# Core_Analogue_Inputs.net
KiCad netlist of a schematic drawn in Altium Designer
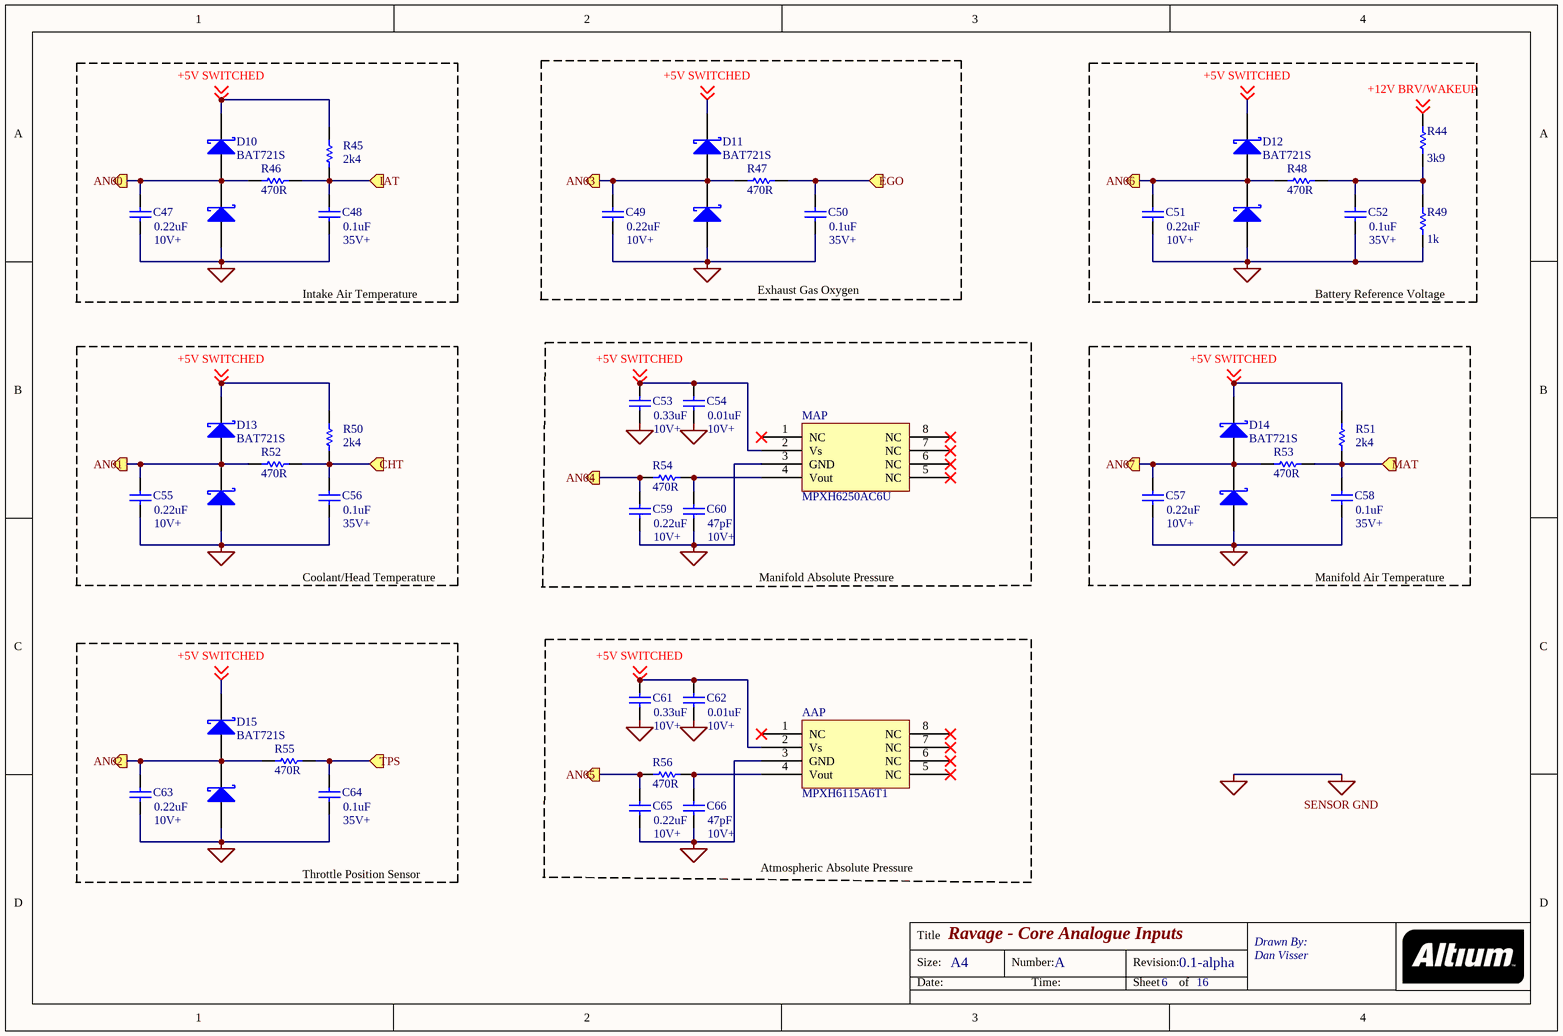
[diagram p0: Core Analogue Inputs.SchDoc]

(export (version "E")
  (design (tool "Eeschema 10.0.6"))
  (components
    (comp (ref "AAP")
      (value "MPXH6115A6T1")
      (libsource (lib "FreeEMS Schematic Library") (part "MPXH6115A6T1"))
    )
    (comp (ref "C47")
      (value "0.22uF")
      (footprint "RAD-0.3")
      (description "Capacitor")
      (fields (field (name "PUBLISHER") "Altium Limited"))
      (libsource (lib "Miscellaneous Devices") (part "Cap"))
    )
    (comp (ref "C48")
      (value "0.1uF")
      (footprint "RAD-0.3")
      (description "Capacitor")
      (fields (field (name "PUBLISHER") "Altium Limited"))
      (libsource (lib "Miscellaneous Devices") (part "Cap"))
    )
    (comp (ref "C49")
      (value "0.22uF")
      (footprint "RAD-0.3")
      (description "Capacitor")
      (fields (field (name "PUBLISHER") "Altium Limited"))
      (libsource (lib "Miscellaneous Devices") (part "Cap"))
    )
    (comp (ref "C50")
      (value "0.1uF")
      (footprint "RAD-0.3")
      (description "Capacitor")
      (fields (field (name "PUBLISHER") "Altium Limited"))
      (libsource (lib "Miscellaneous Devices") (part "Cap"))
    )
    (comp (ref "C51")
      (value "0.22uF")
      (footprint "RAD-0.3")
      (description "Capacitor")
      (fields (field (name "PUBLISHER") "Altium Limited"))
      (libsource (lib "Miscellaneous Devices") (part "Cap"))
    )
    (comp (ref "C52")
      (value "0.1uF")
      (footprint "RAD-0.3")
      (description "Capacitor")
      (fields (field (name "PUBLISHER") "Altium Limited"))
      (libsource (lib "Miscellaneous Devices") (part "Cap"))
    )
    (comp (ref "C53")
      (value "0.33uF")
      (footprint "RAD-0.3")
      (description "Capacitor")
      (fields (field (name "PUBLISHER") "Altium Limited"))
      (libsource (lib "Miscellaneous Devices") (part "Cap"))
    )
    (comp (ref "C54")
      (value "0.01uF")
      (footprint "RAD-0.3")
      (description "Capacitor")
      (fields (field (name "PUBLISHER") "Altium Limited"))
      (libsource (lib "Miscellaneous Devices") (part "Cap"))
    )
    (comp (ref "C55")
      (value "0.22uF")
      (footprint "RAD-0.3")
      (description "Capacitor")
      (fields (field (name "PUBLISHER") "Altium Limited"))
      (libsource (lib "Miscellaneous Devices") (part "Cap"))
    )
    (comp (ref "C56")
      (value "0.1uF")
      (footprint "RAD-0.3")
      (description "Capacitor")
      (fields (field (name "PUBLISHER") "Altium Limited"))
      (libsource (lib "Miscellaneous Devices") (part "Cap"))
    )
    (comp (ref "C57")
      (value "0.22uF")
      (footprint "RAD-0.3")
      (description "Capacitor")
      (fields (field (name "PUBLISHER") "Altium Limited"))
      (libsource (lib "Miscellaneous Devices") (part "Cap"))
    )
    (comp (ref "C58")
      (value "0.1uF")
      (footprint "RAD-0.3")
      (description "Capacitor")
      (fields (field (name "PUBLISHER") "Altium Limited"))
      (libsource (lib "Miscellaneous Devices") (part "Cap"))
    )
    (comp (ref "C59")
      (value "0.22uF")
      (footprint "RAD-0.3")
      (description "Capacitor")
      (fields (field (name "PUBLISHER") "Altium Limited"))
      (libsource (lib "Miscellaneous Devices") (part "Cap"))
    )
    (comp (ref "C60")
      (value "47pF")
      (footprint "RAD-0.3")
      (description "Capacitor")
      (fields (field (name "PUBLISHER") "Altium Limited"))
      (libsource (lib "Miscellaneous Devices") (part "Cap"))
    )
    (comp (ref "C61")
      (value "0.33uF")
      (footprint "RAD-0.3")
      (description "Capacitor")
      (fields (field (name "PUBLISHER") "Altium Limited"))
      (libsource (lib "Miscellaneous Devices") (part "Cap"))
    )
    (comp (ref "C62")
      (value "0.01uF")
      (footprint "RAD-0.3")
      (description "Capacitor")
      (fields (field (name "PUBLISHER") "Altium Limited"))
      (libsource (lib "Miscellaneous Devices") (part "Cap"))
    )
    (comp (ref "C63")
      (value "0.22uF")
      (footprint "RAD-0.3")
      (description "Capacitor")
      (fields (field (name "PUBLISHER") "Altium Limited"))
      (libsource (lib "Miscellaneous Devices") (part "Cap"))
    )
    (comp (ref "C64")
      (value "0.1uF")
      (footprint "RAD-0.3")
      (description "Capacitor")
      (fields (field (name "PUBLISHER") "Altium Limited"))
      (libsource (lib "Miscellaneous Devices") (part "Cap"))
    )
    (comp (ref "C65")
      (value "0.22uF")
      (footprint "RAD-0.3")
      (description "Capacitor")
      (fields (field (name "PUBLISHER") "Altium Limited"))
      (libsource (lib "Miscellaneous Devices") (part "Cap"))
    )
    (comp (ref "C66")
      (value "47pF")
      (footprint "RAD-0.3")
      (description "Capacitor")
      (fields (field (name "PUBLISHER") "Altium Limited"))
      (libsource (lib "Miscellaneous Devices") (part "Cap"))
    )
    (comp (ref "D10")
      (value "BAT721S")
      (description "DUAL SCHOTTKY DIODE")
      (libsource (lib "FreeEMS Schematic Library") (part "BAT721S"))
    )
    (comp (ref "D11")
      (value "BAT721S")
      (description "DUAL SCHOTTKY DIODE")
      (libsource (lib "FreeEMS Schematic Library") (part "BAT721S"))
    )
    (comp (ref "D12")
      (value "BAT721S")
      (description "DUAL SCHOTTKY DIODE")
      (libsource (lib "FreeEMS Schematic Library") (part "BAT721S"))
    )
    (comp (ref "D13")
      (value "BAT721S")
      (description "DUAL SCHOTTKY DIODE")
      (libsource (lib "FreeEMS Schematic Library") (part "BAT721S"))
    )
    (comp (ref "D14")
      (value "BAT721S")
      (description "DUAL SCHOTTKY DIODE")
      (libsource (lib "FreeEMS Schematic Library") (part "BAT721S"))
    )
    (comp (ref "D15")
      (value "BAT721S")
      (description "DUAL SCHOTTKY DIODE")
      (libsource (lib "FreeEMS Schematic Library") (part "BAT721S"))
    )
    (comp (ref "MAP")
      (value "MPXH6250AC6U")
      (libsource (lib "FreeEMS Schematic Library") (part "MPXH6250AC6U"))
    )
    (comp (ref "R44")
      (value "3k9")
      (footprint "AXIAL-0.3")
      (description "Resistor")
      (fields (field (name "PUBLISHER") "Altium Limited"))
      (libsource (lib "Miscellaneous Devices") (part "Res1"))
    )
    (comp (ref "R45")
      (value "2k4")
      (footprint "AXIAL-0.3")
      (description "Resistor")
      (fields (field (name "PUBLISHER") "Altium Limited"))
      (libsource (lib "Miscellaneous Devices") (part "Res1"))
    )
    (comp (ref "R46")
      (value "470R")
      (footprint "AXIAL-0.3")
      (description "Resistor")
      (fields (field (name "PUBLISHER") "Altium Limited"))
      (libsource (lib "Miscellaneous Devices") (part "Res1"))
    )
    (comp (ref "R47")
      (value "470R")
      (footprint "AXIAL-0.3")
      (description "Resistor")
      (fields (field (name "PUBLISHER") "Altium Limited"))
      (libsource (lib "Miscellaneous Devices") (part "Res1"))
    )
    (comp (ref "R48")
      (value "470R")
      (footprint "AXIAL-0.3")
      (description "Resistor")
      (fields (field (name "PUBLISHER") "Altium Limited"))
      (libsource (lib "Miscellaneous Devices") (part "Res1"))
    )
    (comp (ref "R49")
      (value "1k")
      (footprint "AXIAL-0.3")
      (description "Resistor")
      (fields (field (name "PUBLISHER") "Altium Limited"))
      (libsource (lib "Miscellaneous Devices") (part "Res1"))
    )
    (comp (ref "R50")
      (value "2k4")
      (footprint "AXIAL-0.3")
      (description "Resistor")
      (fields (field (name "PUBLISHER") "Altium Limited"))
      (libsource (lib "Miscellaneous Devices") (part "Res1"))
    )
    (comp (ref "R51")
      (value "2k4")
      (footprint "AXIAL-0.3")
      (description "Resistor")
      (fields (field (name "PUBLISHER") "Altium Limited"))
      (libsource (lib "Miscellaneous Devices") (part "Res1"))
    )
    (comp (ref "R52")
      (value "470R")
      (footprint "AXIAL-0.3")
      (description "Resistor")
      (fields (field (name "PUBLISHER") "Altium Limited"))
      (libsource (lib "Miscellaneous Devices") (part "Res1"))
    )
    (comp (ref "R53")
      (value "470R")
      (footprint "AXIAL-0.3")
      (description "Resistor")
      (fields (field (name "PUBLISHER") "Altium Limited"))
      (libsource (lib "Miscellaneous Devices") (part "Res1"))
    )
    (comp (ref "R54")
      (value "470R")
      (footprint "AXIAL-0.3")
      (description "Resistor")
      (fields (field (name "PUBLISHER") "Altium Limited"))
      (libsource (lib "Miscellaneous Devices") (part "Res1"))
    )
    (comp (ref "R55")
      (value "470R")
      (footprint "AXIAL-0.3")
      (description "Resistor")
      (fields (field (name "PUBLISHER") "Altium Limited"))
      (libsource (lib "Miscellaneous Devices") (part "Res1"))
    )
    (comp (ref "R56")
      (value "470R")
      (footprint "AXIAL-0.3")
      (description "Resistor")
      (fields (field (name "PUBLISHER") "Altium Limited"))
      (libsource (lib "Miscellaneous Devices") (part "Res1"))
    )
  )
  (nets
    (net (code "1") (name "+5V SWITCHED") (class "Default")
      (node (ref "AAP") (pin "2") (pinfunction "Vs_2") (pintype "passive"))
      (node (ref "C53") (pin "2") (pinfunction "2_2") (pintype "passive"))
      (node (ref "C54") (pin "2") (pinfunction "2_2") (pintype "passive"))
      (node (ref "C61") (pin "2") (pinfunction "2_2") (pintype "passive"))
      (node (ref "C62") (pin "2") (pinfunction "2_2") (pintype "passive"))
      (node (ref "D10") (pin "2") (pinfunction "K_2") (pintype "passive"))
      (node (ref "D11") (pin "2") (pinfunction "K_2") (pintype "passive"))
      (node (ref "D12") (pin "2") (pinfunction "K_2") (pintype "passive"))
      (node (ref "D13") (pin "2") (pinfunction "K_2") (pintype "passive"))
      (node (ref "D14") (pin "2") (pinfunction "K_2") (pintype "passive"))
      (node (ref "D15") (pin "2") (pinfunction "K_2") (pintype "passive"))
      (node (ref "MAP") (pin "2") (pinfunction "Vs_2") (pintype "passive"))
      (node (ref "R45") (pin "1") (pinfunction "1_1") (pintype "passive"))
      (node (ref "R50") (pin "1") (pinfunction "1_1") (pintype "passive"))
      (node (ref "R51") (pin "1") (pinfunction "1_1") (pintype "passive"))
    )
    (net (code "2") (name "+12V BRV{slash}WAKEUP") (class "Default")
      (node (ref "R44") (pin "2") (pinfunction "2_2") (pintype "passive"))
    )
    (net (code "3") (name "/AN00") (class "Default")
      (node (ref "C47") (pin "2") (pinfunction "2_2") (pintype "passive"))
      (node (ref "D10") (pin "3") (pinfunction "A2_3") (pintype "passive"))
      (node (ref "R46") (pin "1") (pinfunction "1_1") (pintype "passive"))
    )
    (net (code "4") (name "/AN01") (class "Default")
      (node (ref "C55") (pin "2") (pinfunction "2_2") (pintype "passive"))
      (node (ref "D13") (pin "3") (pinfunction "A2_3") (pintype "passive"))
      (node (ref "R52") (pin "1") (pinfunction "1_1") (pintype "passive"))
    )
    (net (code "5") (name "/AN02") (class "Default")
      (node (ref "C63") (pin "2") (pinfunction "2_2") (pintype "passive"))
      (node (ref "D15") (pin "3") (pinfunction "A2_3") (pintype "passive"))
      (node (ref "R55") (pin "1") (pinfunction "1_1") (pintype "passive"))
    )
    (net (code "6") (name "/AN03") (class "Default")
      (node (ref "C49") (pin "2") (pinfunction "2_2") (pintype "passive"))
      (node (ref "D11") (pin "3") (pinfunction "A2_3") (pintype "passive"))
      (node (ref "R47") (pin "1") (pinfunction "1_1") (pintype "passive"))
    )
    (net (code "7") (name "/AN04") (class "Default")
      (node (ref "C59") (pin "2") (pinfunction "2_2") (pintype "passive"))
      (node (ref "R54") (pin "1") (pinfunction "1_1") (pintype "passive"))
    )
    (net (code "8") (name "/AN05") (class "Default")
      (node (ref "C65") (pin "2") (pinfunction "2_2") (pintype "passive"))
      (node (ref "R56") (pin "1") (pinfunction "1_1") (pintype "passive"))
    )
    (net (code "9") (name "/AN06") (class "Default")
      (node (ref "C51") (pin "2") (pinfunction "2_2") (pintype "passive"))
      (node (ref "D12") (pin "3") (pinfunction "A2_3") (pintype "passive"))
      (node (ref "R48") (pin "1") (pinfunction "1_1") (pintype "passive"))
    )
    (net (code "10") (name "/AN07") (class "Default")
      (node (ref "C57") (pin "2") (pinfunction "2_2") (pintype "passive"))
      (node (ref "D14") (pin "3") (pinfunction "A2_3") (pintype "passive"))
      (node (ref "R53") (pin "1") (pinfunction "1_1") (pintype "passive"))
    )
    (net (code "11") (name "/CHT") (class "Default")
      (node (ref "C56") (pin "2") (pinfunction "2_2") (pintype "passive"))
      (node (ref "R50") (pin "2") (pinfunction "2_2") (pintype "passive"))
      (node (ref "R52") (pin "2") (pinfunction "2_2") (pintype "passive"))
    )
    (net (code "12") (name "/EGO") (class "Default")
      (node (ref "C50") (pin "2") (pinfunction "2_2") (pintype "passive"))
      (node (ref "R47") (pin "2") (pinfunction "2_2") (pintype "passive"))
    )
    (net (code "13") (name "/IAT") (class "Default")
      (node (ref "C48") (pin "2") (pinfunction "2_2") (pintype "passive"))
      (node (ref "R45") (pin "2") (pinfunction "2_2") (pintype "passive"))
      (node (ref "R46") (pin "2") (pinfunction "2_2") (pintype "passive"))
    )
    (net (code "14") (name "/MAT") (class "Default")
      (node (ref "C58") (pin "2") (pinfunction "2_2") (pintype "passive"))
      (node (ref "R51") (pin "2") (pinfunction "2_2") (pintype "passive"))
      (node (ref "R53") (pin "2") (pinfunction "2_2") (pintype "passive"))
    )
    (net (code "15") (name "/TPS") (class "Default")
      (node (ref "C64") (pin "2") (pinfunction "2_2") (pintype "passive"))
      (node (ref "R55") (pin "2") (pinfunction "2_2") (pintype "passive"))
    )
    (net (code "16") (name "<NO NET>") (class "Default")
      (node (ref "AAP") (pin "3") (pinfunction "GND_3") (pintype "passive"))
      (node (ref "C47") (pin "1") (pinfunction "1_1") (pintype "passive"))
      (node (ref "C48") (pin "1") (pinfunction "1_1") (pintype "passive"))
      (node (ref "C49") (pin "1") (pinfunction "1_1") (pintype "passive"))
      (node (ref "C50") (pin "1") (pinfunction "1_1") (pintype "passive"))
      (node (ref "C51") (pin "1") (pinfunction "1_1") (pintype "passive"))
      (node (ref "C52") (pin "1") (pinfunction "1_1") (pintype "passive"))
      (node (ref "C53") (pin "1") (pinfunction "1_1") (pintype "passive"))
      (node (ref "C54") (pin "1") (pinfunction "1_1") (pintype "passive"))
      (node (ref "C55") (pin "1") (pinfunction "1_1") (pintype "passive"))
      (node (ref "C56") (pin "1") (pinfunction "1_1") (pintype "passive"))
      (node (ref "C57") (pin "1") (pinfunction "1_1") (pintype "passive"))
      (node (ref "C58") (pin "1") (pinfunction "1_1") (pintype "passive"))
      (node (ref "C59") (pin "1") (pinfunction "1_1") (pintype "passive"))
      (node (ref "C60") (pin "1") (pinfunction "1_1") (pintype "passive"))
      (node (ref "C61") (pin "1") (pinfunction "1_1") (pintype "passive"))
      (node (ref "C62") (pin "1") (pinfunction "1_1") (pintype "passive"))
      (node (ref "C63") (pin "1") (pinfunction "1_1") (pintype "passive"))
      (node (ref "C64") (pin "1") (pinfunction "1_1") (pintype "passive"))
      (node (ref "C65") (pin "1") (pinfunction "1_1") (pintype "passive"))
      (node (ref "C66") (pin "1") (pinfunction "1_1") (pintype "passive"))
      (node (ref "D10") (pin "1") (pinfunction "A_1") (pintype "passive"))
      (node (ref "D11") (pin "1") (pinfunction "A_1") (pintype "passive"))
      (node (ref "D12") (pin "1") (pinfunction "A_1") (pintype "passive"))
      (node (ref "D13") (pin "1") (pinfunction "A_1") (pintype "passive"))
      (node (ref "D14") (pin "1") (pinfunction "A_1") (pintype "passive"))
      (node (ref "D15") (pin "1") (pinfunction "A_1") (pintype "passive"))
      (node (ref "MAP") (pin "3") (pinfunction "GND_3") (pintype "passive"))
      (node (ref "R49") (pin "1") (pinfunction "1_1") (pintype "passive"))
    )
    (net (code "17") (name "Net-(AAP-Vout)") (class "Default")
      (node (ref "AAP") (pin "4") (pinfunction "Vout_4") (pintype "passive"))
      (node (ref "C66") (pin "2") (pinfunction "2_2") (pintype "passive"))
      (node (ref "R56") (pin "2") (pinfunction "2_2") (pintype "passive"))
    )
    (net (code "18") (name "Net-(C52-Pad2)") (class "Default")
      (node (ref "C52") (pin "2") (pinfunction "2_2") (pintype "passive"))
      (node (ref "R44") (pin "1") (pinfunction "1_1") (pintype "passive"))
      (node (ref "R48") (pin "2") (pinfunction "2_2") (pintype "passive"))
      (node (ref "R49") (pin "2") (pinfunction "2_2") (pintype "passive"))
    )
    (net (code "19") (name "Net-(MAP-Vout)") (class "Default")
      (node (ref "C60") (pin "2") (pinfunction "2_2") (pintype "passive"))
      (node (ref "MAP") (pin "4") (pinfunction "Vout_4") (pintype "passive"))
      (node (ref "R54") (pin "2") (pinfunction "2_2") (pintype "passive"))
    )
    (net (code "20") (name "unconnected-(AAP-NC-Pad1)") (class "Default")
      (node (ref "AAP") (pin "1") (pinfunction "NC_1") (pintype "passive+no_connect"))
    )
    (net (code "21") (name "unconnected-(AAP-NC-Pad5)") (class "Default")
      (node (ref "AAP") (pin "5") (pinfunction "NC_5") (pintype "passive+no_connect"))
    )
    (net (code "22") (name "unconnected-(AAP-NC-Pad6)") (class "Default")
      (node (ref "AAP") (pin "6") (pinfunction "NC_6") (pintype "passive+no_connect"))
    )
    (net (code "23") (name "unconnected-(AAP-NC-Pad7)") (class "Default")
      (node (ref "AAP") (pin "7") (pinfunction "NC_7") (pintype "passive+no_connect"))
    )
    (net (code "24") (name "unconnected-(AAP-NC-Pad8)") (class "Default")
      (node (ref "AAP") (pin "8") (pinfunction "NC_8") (pintype "passive+no_connect"))
    )
    (net (code "25") (name "unconnected-(MAP-NC-Pad1)") (class "Default")
      (node (ref "MAP") (pin "1") (pinfunction "NC_1") (pintype "passive+no_connect"))
    )
    (net (code "26") (name "unconnected-(MAP-NC-Pad5)") (class "Default")
      (node (ref "MAP") (pin "5") (pinfunction "NC_5") (pintype "passive+no_connect"))
    )
    (net (code "27") (name "unconnected-(MAP-NC-Pad6)") (class "Default")
      (node (ref "MAP") (pin "6") (pinfunction "NC_6") (pintype "passive+no_connect"))
    )
    (net (code "28") (name "unconnected-(MAP-NC-Pad7)") (class "Default")
      (node (ref "MAP") (pin "7") (pinfunction "NC_7") (pintype "passive+no_connect"))
    )
    (net (code "29") (name "unconnected-(MAP-NC-Pad8)") (class "Default")
      (node (ref "MAP") (pin "8") (pinfunction "NC_8") (pintype "passive+no_connect"))
    )
  )
)
